# OpAmpDiffHSC.net
KiCad netlist of a schematic drawn in Altium Designer
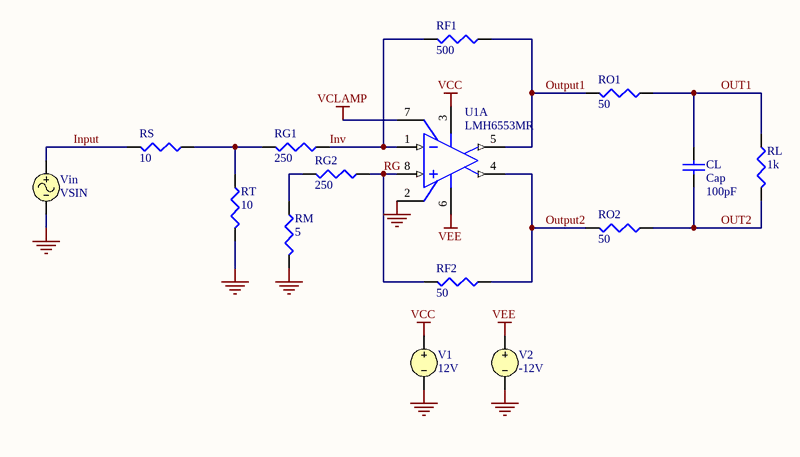
[diagram p0: OpAmpDiffHSC.schdoc]

(export (version "E")
  (design (tool "Eeschema 10.0.6"))
  (components
    (comp (ref "CL")
      (value "Cap")
      (footprint "RAD-0.3")
      (description "Capacitor")
      (fields (field (name "ALTIUM_VALUE") "100pF") (field (name "PUBLISHER") "Altium Limited"))
      (libsource (lib "Miscellaneous Devices") (part "Cap"))
    )
    (comp (ref "RF1")
      (value "500")
      (description "Resistor")
      (fields (field (name "Comment") "100k"))
      (libsource (lib "*") (part "RES"))
    )
    (comp (ref "RF2")
      (value "50")
      (description "Resistor")
      (fields (field (name "Comment") "100k"))
      (libsource (lib "*") (part "RES"))
    )
    (comp (ref "RG1")
      (value "250")
      (description "Resistor")
      (fields (field (name "Comment") "10k"))
      (libsource (lib "*") (part "RES"))
    )
    (comp (ref "RG2")
      (value "250")
      (description "Resistor")
      (fields (field (name "Comment") "10k"))
      (libsource (lib "*") (part "RES"))
    )
    (comp (ref "RL")
      (value "1k")
      (description "Resistor")
      (fields (field (name "Comment") "25k"))
      (libsource (lib "") (part "RES_1"))
    )
    (comp (ref "RM")
      (value "5")
      (description "Resistor")
      (fields (field (name "Comment") "10k"))
      (libsource (lib "") (part "RES_1"))
    )
    (comp (ref "RO1")
      (value "50")
      (description "Resistor")
      (fields (field (name "Comment") "25k"))
      (libsource (lib "*") (part "RES"))
    )
    (comp (ref "RO2")
      (value "50")
      (description "Resistor")
      (fields (field (name "Comment") "25k"))
      (libsource (lib "*") (part "RES"))
    )
    (comp (ref "RS")
      (value "10")
      (description "Resistor")
      (fields (field (name "Comment") "10k"))
      (libsource (lib "*") (part "RES"))
    )
    (comp (ref "RT")
      (value "10")
      (description "Resistor")
      (fields (field (name "Comment") "10k"))
      (libsource (lib "") (part "RES_1"))
    )
    (comp (ref "U1")
      (value "LMH6553MR")
      (footprint "MRA08B_N")
      (description "900 MHz Fully Differential Amplifier with Output Limiting Clamp")
      (fields
        (field (name "PARTNUMBER") "LMH6553")
        (field (name "MANUFACTURER") "National Semiconductor")
        (field (name "PUBLISHER") "Altium Limited")
      )
      (libsource (lib "NSC Amplifier with SIM models") (part "LMH6553MR"))
    )
    (comp (ref "V1") (value "12V") (description "Voltage Source") (libsource (lib "*") (part "VSRC")))
    (comp (ref "V2") (value "-12V") (description "Voltage Source") (libsource (lib "*") (part "VSRC")))
    (comp (ref "Vin")
      (value "VSIN")
      (description "Sinusoidal Voltage Source")
      (libsource (lib "*") (part "VSIN"))
    )
  )
  (nets
    (net (code "1") (name "/Input") (class "Default")
      (node (ref "RS") (pin "1") (pinfunction "TOP_1") (pintype "passive"))
      (node (ref "Vin") (pin "1") (pinfunction "1_1") (pintype "passive"))
    )
    (net (code "2") (name "/Inv") (class "Default")
      (node (ref "RF1") (pin "1") (pinfunction "TOP_1") (pintype "passive"))
      (node (ref "RG1") (pin "2") (pinfunction "BOT_2") (pintype "passive"))
      (node (ref "U1") (pin "1") (pinfunction "IN-_1") (pintype "input"))
    )
    (net (code "3") (name "/OUT1") (class "Default")
      (node (ref "CL") (pin "2") (pinfunction "2_2") (pintype "passive"))
      (node (ref "RL") (pin "2") (pinfunction "BOT_2") (pintype "passive"))
      (node (ref "RO1") (pin "2") (pinfunction "BOT_2") (pintype "passive"))
    )
    (net (code "4") (name "/OUT2") (class "Default")
      (node (ref "CL") (pin "1") (pinfunction "1_1") (pintype "passive"))
      (node (ref "RL") (pin "1") (pinfunction "TOP_1") (pintype "passive"))
      (node (ref "RO2") (pin "2") (pinfunction "BOT_2") (pintype "passive"))
    )
    (net (code "5") (name "/Output1") (class "Default")
      (node (ref "RF1") (pin "2") (pinfunction "BOT_2") (pintype "passive"))
      (node (ref "RO1") (pin "1") (pinfunction "TOP_1") (pintype "passive"))
      (node (ref "U1") (pin "5") (pinfunction "OUT-_5") (pintype "output"))
    )
    (net (code "6") (name "/Output2") (class "Default")
      (node (ref "RF2") (pin "2") (pinfunction "BOT_2") (pintype "passive"))
      (node (ref "RO2") (pin "1") (pinfunction "TOP_1") (pintype "passive"))
      (node (ref "U1") (pin "4") (pinfunction "OUT+_4") (pintype "output"))
    )
    (net (code "7") (name "/RG") (class "Default")
      (node (ref "RF2") (pin "1") (pinfunction "TOP_1") (pintype "passive"))
      (node (ref "RG2") (pin "2") (pinfunction "BOT_2") (pintype "passive"))
      (node (ref "U1") (pin "8") (pinfunction "IN+_8") (pintype "input"))
    )
    (net (code "8") (name "GND") (class "Default")
      (node (ref "RM") (pin "1") (pinfunction "TOP_1") (pintype "passive"))
      (node (ref "RT") (pin "1") (pinfunction "TOP_1") (pintype "passive"))
      (node (ref "U1") (pin "2") (pinfunction "VCM_2") (pintype "passive"))
      (node (ref "V1") (pin "2") (pinfunction "2_2") (pintype "passive"))
      (node (ref "V2") (pin "2") (pinfunction "2_2") (pintype "passive"))
      (node (ref "Vin") (pin "2") (pinfunction "2_2") (pintype "passive"))
    )
    (net (code "9") (name "Net-(RG1-TOP)") (class "Default")
      (node (ref "RG1") (pin "1") (pinfunction "TOP_1") (pintype "passive"))
      (node (ref "RS") (pin "2") (pinfunction "BOT_2") (pintype "passive"))
      (node (ref "RT") (pin "2") (pinfunction "BOT_2") (pintype "passive"))
    )
    (net (code "10") (name "Net-(RG2-TOP)") (class "Default")
      (node (ref "RG2") (pin "1") (pinfunction "TOP_1") (pintype "passive"))
      (node (ref "RM") (pin "2") (pinfunction "BOT_2") (pintype "passive"))
    )
    (net (code "11") (name "VCC") (class "Default")
      (node (ref "U1") (pin "3") (pinfunction "V+_3") (pintype "power_in"))
      (node (ref "V1") (pin "1") (pinfunction "1_1") (pintype "passive"))
    )
    (net (code "12") (name "VCLAMP") (class "Default")
      (node (ref "U1") (pin "7") (pinfunction "VCLAMP_7") (pintype "passive"))
    )
    (net (code "13") (name "VEE") (class "Default")
      (node (ref "U1") (pin "6") (pinfunction "V-_6") (pintype "power_in"))
      (node (ref "V2") (pin "1") (pinfunction "1_1") (pintype "passive"))
    )
  )
)
